# Pedal_PCB.net
KiCad netlist of a schematic drawn in EAGLE
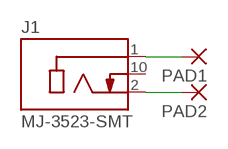
[diagram p0: schematic, sheet 1]

(export (version "E")
  (design (tool "Eeschema 10.0.6"))
  (components
    (comp (ref "J1")
      (value "MJ-3523-SMT")
      (footprint "eagle-import:CUI_MJ-3523-SMT")
      (fields (field (name "MANUFACTURER") "CUI INC"))
      (libsource (lib "eagle-import") (part "MJ-3523-SMT"))
    )
    (comp (ref "PAD1")
      (value "SMD2")
      (footprint "eagle-import:SMD1,27-2,54")
      (libsource (lib "eagle-import") (part "SMD2"))
    )
    (comp (ref "PAD2")
      (value "SMD2")
      (footprint "eagle-import:SMD1,27-2,54")
      (libsource (lib "eagle-import") (part "SMD2"))
    )
  )
  (nets
    (net (code "1") (name "Net-(PAD1-P)") (class "Default")
      (node (ref "J1") (pin "1") (pinfunction "1_1") (pintype "passive"))
      (node (ref "PAD1") (pin "1") (pinfunction "P_1") (pintype "passive"))
    )
    (net (code "2") (name "Net-(PAD2-P)") (class "Default")
      (node (ref "J1") (pin "2") (pinfunction "2_2") (pintype "passive"))
      (node (ref "PAD2") (pin "1") (pinfunction "P_1") (pintype "passive"))
    )
    (net (code "3") (name "unconnected-(J1-Pad10)") (class "Default")
      (node (ref "J1") (pin "10") (pinfunction "10_10") (pintype "passive"))
    )
  )
)
